# RECEIVER_DORJI7020.net
KiCad netlist of a schematic drawn in Altium Designer
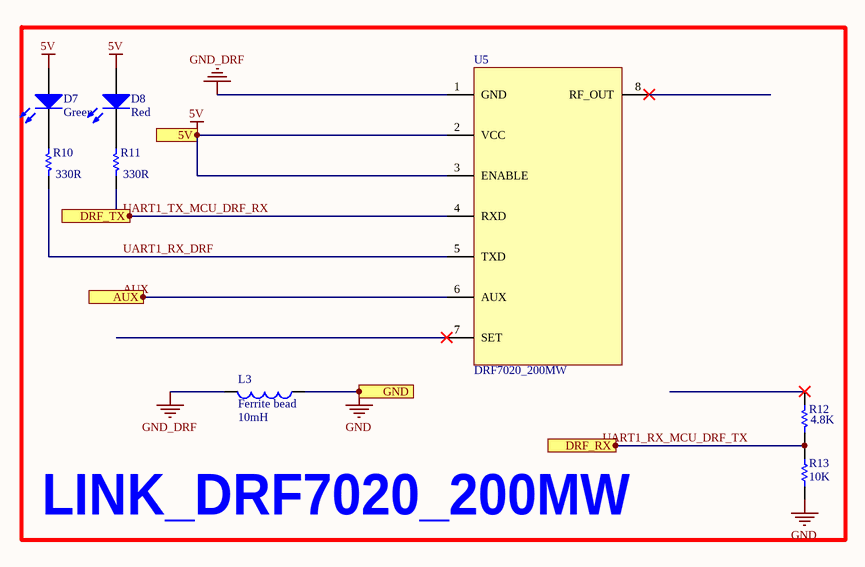
[diagram p0: RECEIVER_DORJI7020.SchDoc]

(export (version "E")
  (design (tool "Eeschema 10.0.6"))
  (components
    (comp (ref "D7")
      (value "Green")
      (footprint "0603 -LED_GREEN - duplicate")
      (description "Typical INFRARED GaAs LED")
      (fields (field (name "PUBLISHER") "Altium Limited"))
      (libsource (lib "Miscellaneous Devices") (part "LED0"))
    )
    (comp (ref "D8")
      (value "Red")
      (footprint "0603 -LED_GREEN - duplicate")
      (description "Typical INFRARED GaAs LED")
      (fields (field (name "PUBLISHER") "Altium Limited"))
      (libsource (lib "Miscellaneous Devices") (part "LED0"))
    )
    (comp (ref "L3")
      (value "Ferrite bead")
      (footprint "0603 - RESISTOR")
      (description "Inductor")
      (fields (field (name "ALTIUM_VALUE") "10mH") (field (name "PUBLISHER") "Altium Limited"))
      (libsource (lib "Miscellaneous Devices") (part "Inductor"))
    )
    (comp (ref "R10")
      (value "330R")
      (footprint "0603 - RESISTOR")
      (description "Resistor")
      (fields (field (name "PUBLISHER") "Altium Limited"))
      (libsource (lib "Miscellaneous Devices") (part "Res1"))
    )
    (comp (ref "R11")
      (value "330R")
      (footprint "0603 - RESISTOR")
      (description "Resistor")
      (fields (field (name "PUBLISHER") "Altium Limited"))
      (libsource (lib "Miscellaneous Devices") (part "Res1"))
    )
    (comp (ref "R12")
      (value "4.8K")
      (footprint "0603 - RESISTOR")
      (description "Resistor")
      (fields (field (name "PUBLISHER") "Altium Limited"))
      (libsource (lib "Miscellaneous Devices") (part "Res1"))
    )
    (comp (ref "R13")
      (value "10K")
      (footprint "0603 - RESISTOR")
      (description "Semiconductor Resistor")
      (fields (field (name "PUBLISHER") "Altium Limited"))
      (libsource (lib "Miscellaneous Devices") (part "Res Semi"))
    )
    (comp (ref "U5")
      (value "DRF7020_200MW")
      (footprint "DRF7020D13_MODULE_200MW")
      (libsource (lib "My_Shematic_library") (part "DRF7020_200MW"))
    )
  )
  (nets
    (net (code "1") (name "/AUX") (class "Default")
      (node (ref "U5") (pin "6") (pinfunction "AUX_6") (pintype "power_in"))
    )
    (net (code "2") (name "/UART1_RX_DRF") (class "Default")
      (node (ref "R10") (pin "2") (pinfunction "2_2") (pintype "passive"))
      (node (ref "U5") (pin "5") (pinfunction "TXD_5") (pintype "power_in"))
    )
    (net (code "3") (name "/UART1_RX_MCU_DRF_TX") (class "Default")
      (node (ref "R12") (pin "2") (pinfunction "2_2") (pintype "passive"))
      (node (ref "R13") (pin "1") (pinfunction "1_1") (pintype "passive"))
    )
    (net (code "4") (name "/UART1_TX_MCU_DRF_RX") (class "Default")
      (node (ref "R11") (pin "2") (pinfunction "2_2") (pintype "passive"))
      (node (ref "U5") (pin "4") (pinfunction "RXD_4") (pintype "power_in"))
    )
    (net (code "5") (name "5V") (class "Default")
      (node (ref "D7") (pin "1") (pinfunction "A_1") (pintype "passive"))
      (node (ref "D8") (pin "1") (pinfunction "A_1") (pintype "passive"))
      (node (ref "U5") (pin "2") (pinfunction "VCC_2") (pintype "power_in"))
      (node (ref "U5") (pin "3") (pinfunction "ENABLE_3") (pintype "power_in"))
    )
    (net (code "6") (name "GND") (class "Default")
      (node (ref "L3") (pin "1") (pinfunction "1_1") (pintype "passive"))
      (node (ref "R13") (pin "2") (pinfunction "2_2") (pintype "passive"))
    )
    (net (code "7") (name "GND_DRF") (class "Default")
      (node (ref "L3") (pin "2") (pinfunction "2_2") (pintype "passive"))
      (node (ref "U5") (pin "1") (pinfunction "GND_1") (pintype "power_in"))
    )
    (net (code "8") (name "Net-(D7-K)") (class "Default")
      (node (ref "D7") (pin "2") (pinfunction "K_2") (pintype "passive"))
      (node (ref "R10") (pin "1") (pinfunction "1_1") (pintype "passive"))
    )
    (net (code "9") (name "Net-(D8-K)") (class "Default")
      (node (ref "D8") (pin "2") (pinfunction "K_2") (pintype "passive"))
      (node (ref "R11") (pin "1") (pinfunction "1_1") (pintype "passive"))
    )
    (net (code "10") (name "unconnected-(R12-Pad1)") (class "Default")
      (node (ref "R12") (pin "1") (pinfunction "1_1") (pintype "passive+no_connect"))
    )
    (net (code "11") (name "unconnected-(U5-RF_OUT-Pad8)") (class "Default")
      (node (ref "U5") (pin "8") (pinfunction "RF_OUT_8") (pintype "power_in+no_connect"))
    )
    (net (code "12") (name "unconnected-(U5-SET-Pad7)") (class "Default")
      (node (ref "U5") (pin "7") (pinfunction "SET_7") (pintype "power_in+no_connect"))
    )
  )
)
